# SpW_Misc.net
KiCad netlist of a schematic drawn in Altium Designer
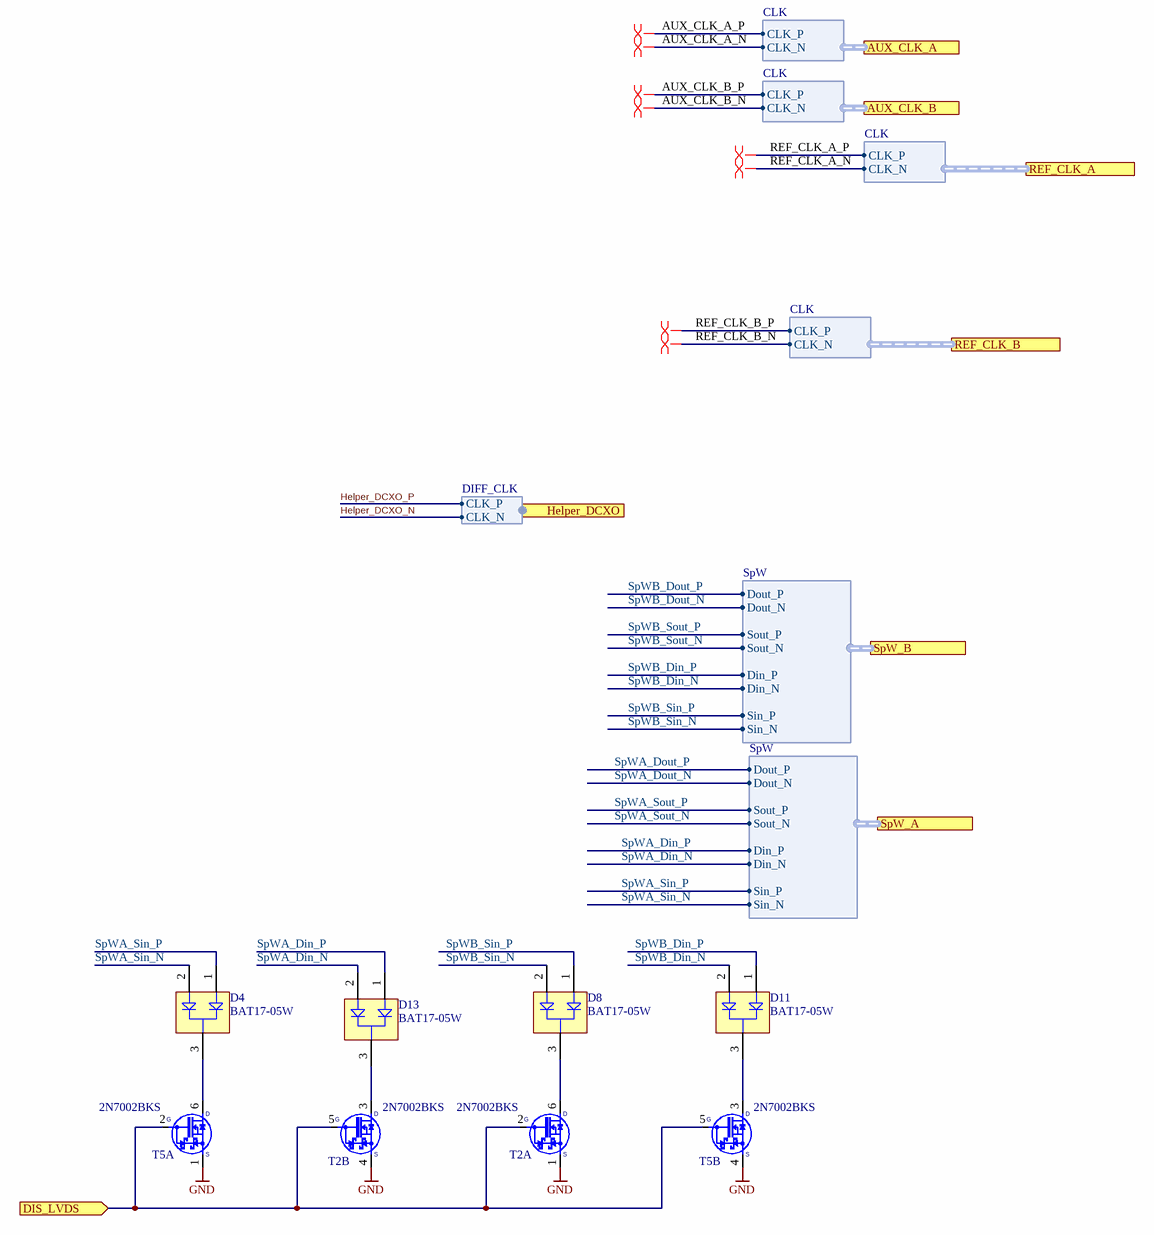
[diagram p0: SpW_Misc.SchDoc]

(export (version "E")
  (design (tool "Eeschema 10.0.6"))
  (components
    (comp (ref "D4")
      (value "BAT17-05W")
      (footprint "INF-SOT323_N")
      (description "Dual Silicon Schottky Diode, 130 mA IF Max, SOT323, Green")
      (fields (field (name "MANUFACTURER") "Infineon"))
      (libsource (lib "Altium Content Vault") (part "INF-D_A1A2K3-3"))
    )
    (comp (ref "D8")
      (value "BAT17-05W")
      (footprint "INF-SOT323_N")
      (description "Dual Silicon Schottky Diode, 130 mA IF Max, SOT323, Green")
      (fields (field (name "MANUFACTURER") "Infineon"))
      (libsource (lib "Altium Content Vault") (part "INF-D_A1A2K3-3"))
    )
    (comp (ref "D11")
      (value "BAT17-05W")
      (footprint "INF-SOT323_N")
      (description "Dual Silicon Schottky Diode, 130 mA IF Max, SOT323, Green")
      (fields (field (name "MANUFACTURER") "Infineon"))
      (libsource (lib "Altium Content Vault") (part "INF-D_A1A2K3-3"))
    )
    (comp (ref "D13")
      (value "BAT17-05W")
      (footprint "INF-SOT323_N")
      (description "Dual Silicon Schottky Diode, 130 mA IF Max, SOT323, Green")
      (fields (field (name "MANUFACTURER") "Infineon"))
      (libsource (lib "Altium Content Vault") (part "INF-D_A1A2K3-3"))
    )
    (comp (ref "T2")
      (value "2N7002BKS")
      (footprint "SOT65P210X110-6N")
      (description "60V, 300mA Dual N-Channel Trench MOSFET")
      (fields
        (field (name "MANUFACTURER") "NXP SEMICONDUCTORS")
        (field (name "MANUFACTURER PART NUMBER") "2N7002BKS6")
        (field (name "AUTHOR") "CERN DEM JLC")
      )
      (libsource (lib "ICs And Semiconductors") (part "2N7002BKS"))
    )
    (comp (ref "T5")
      (value "2N7002BKS")
      (footprint "SOT65P210X110-6N")
      (description "60V, 300mA Dual N-Channel Trench MOSFET")
      (fields
        (field (name "MANUFACTURER") "NXP SEMICONDUCTORS")
        (field (name "MANUFACTURER PART NUMBER") "2N7002BKS6")
        (field (name "AUTHOR") "CERN DEM JLC")
      )
      (libsource (lib "ICs And Semiconductors") (part "2N7002BKS"))
    )
  )
  (nets
    (net (code "8") (name "/DIS_LVDS") (class "Default")
      (node (ref "T2") (pin "2") (pinfunction "G_2") (pintype "passive"))
      (node (ref "T2") (pin "5") (pinfunction "G_5") (pintype "passive"))
      (node (ref "T5") (pin "2") (pinfunction "G_2") (pintype "passive"))
      (node (ref "T5") (pin "5") (pinfunction "G_5") (pintype "passive"))
    )
    (net (code "15") (name "/SpWA_Din_N") (class "Default")
      (node (ref "D13") (pin "2") (pinfunction "A2_2") (pintype "passive"))
    )
    (net (code "16") (name "/SpWA_Din_P") (class "Default")
      (node (ref "D13") (pin "1") (pinfunction "A1_1") (pintype "passive"))
    )
    (net (code "19") (name "/SpWA_Sin_N") (class "Default")
      (node (ref "D4") (pin "2") (pinfunction "A2_2") (pintype "passive"))
    )
    (net (code "20") (name "/SpWA_Sin_P") (class "Default")
      (node (ref "D4") (pin "1") (pinfunction "A1_1") (pintype "passive"))
    )
    (net (code "23") (name "/SpWB_Din_N") (class "Default")
      (node (ref "D11") (pin "2") (pinfunction "A2_2") (pintype "passive"))
    )
    (net (code "24") (name "/SpWB_Din_P") (class "Default")
      (node (ref "D11") (pin "1") (pinfunction "A1_1") (pintype "passive"))
    )
    (net (code "27") (name "/SpWB_Sin_N") (class "Default")
      (node (ref "D8") (pin "2") (pinfunction "A2_2") (pintype "passive"))
    )
    (net (code "28") (name "/SpWB_Sin_P") (class "Default")
      (node (ref "D8") (pin "1") (pinfunction "A1_1") (pintype "passive"))
    )
    (net (code "34") (name "GND") (class "Default")
      (node (ref "T2") (pin "1") (pinfunction "S_1") (pintype "passive"))
      (node (ref "T2") (pin "4") (pinfunction "S_4") (pintype "passive"))
      (node (ref "T5") (pin "1") (pinfunction "S_1") (pintype "passive"))
      (node (ref "T5") (pin "4") (pinfunction "S_4") (pintype "passive"))
    )
    (net (code "35") (name "Net-(D4-K)") (class "Default")
      (node (ref "D4") (pin "3") (pinfunction "K_3") (pintype "passive"))
      (node (ref "T5") (pin "6") (pinfunction "D_6") (pintype "passive"))
    )
    (net (code "36") (name "Net-(D8-K)") (class "Default")
      (node (ref "D8") (pin "3") (pinfunction "K_3") (pintype "passive"))
      (node (ref "T2") (pin "6") (pinfunction "D_6") (pintype "passive"))
    )
    (net (code "37") (name "Net-(D11-K)") (class "Default")
      (node (ref "D11") (pin "3") (pinfunction "K_3") (pintype "passive"))
      (node (ref "T5") (pin "3") (pinfunction "D_3") (pintype "passive"))
    )
    (net (code "38") (name "Net-(D13-K)") (class "Default")
      (node (ref "D13") (pin "3") (pinfunction "K_3") (pintype "passive"))
      (node (ref "T2") (pin "3") (pinfunction "D_3") (pintype "passive"))
    )
  )
)
